# ethernet-cp2200.net
KiCad netlist of a schematic drawn in EAGLE
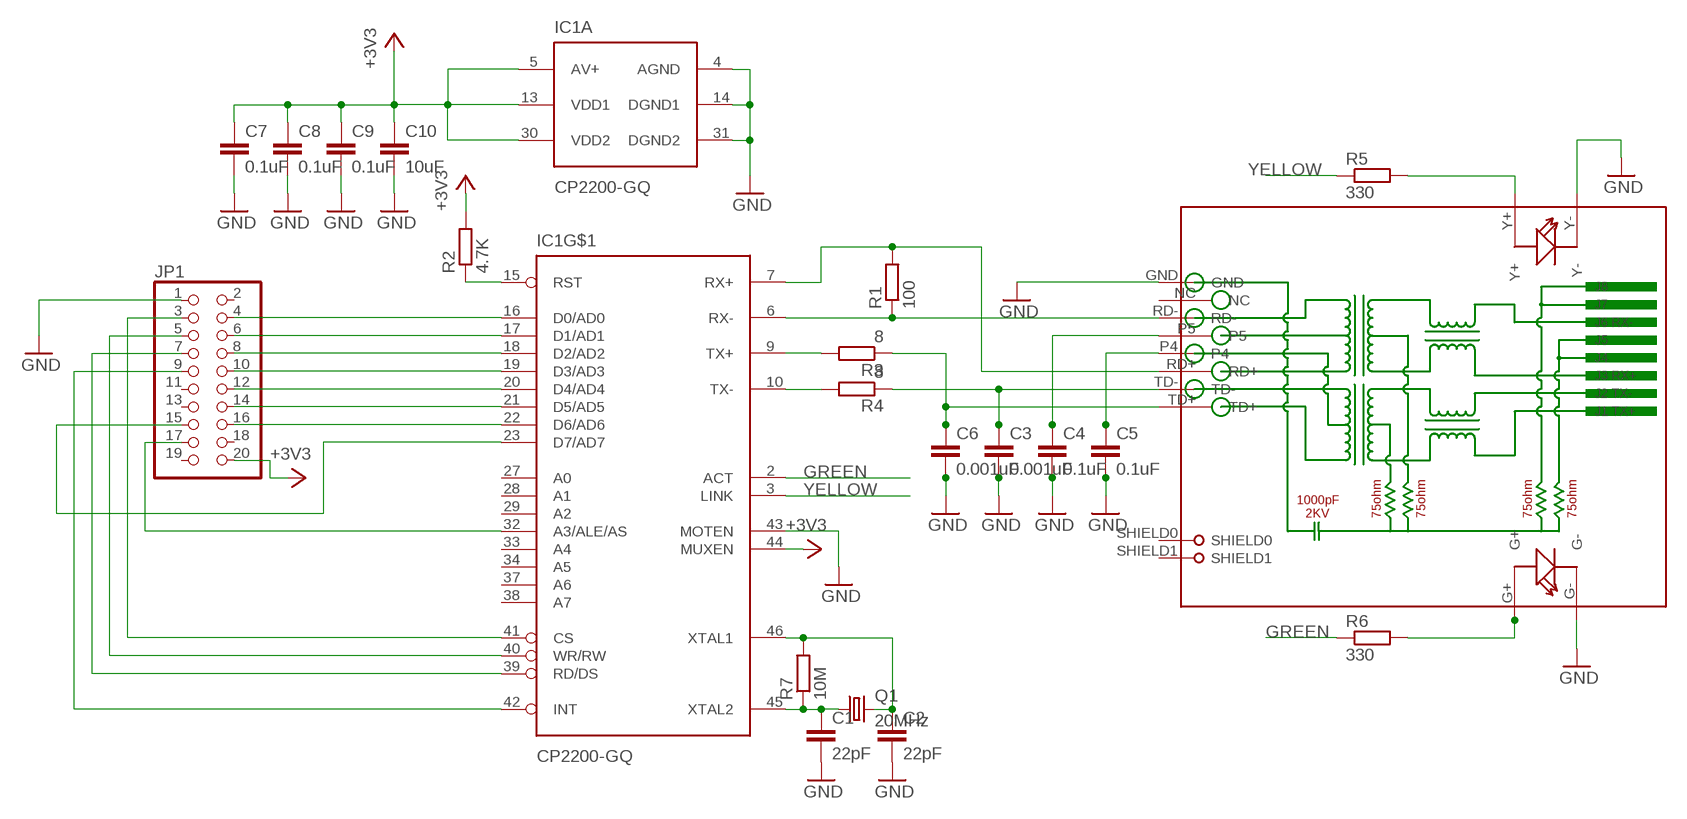
[diagram p0: schematic, sheet 1]

(export (version "E")
  (design (tool "Eeschema 10.0.6"))
  (components
    (comp (ref "C1")
      (value "22pF")
      (footprint "eagle-import:C0805")
      (libsource (lib "eagle-import") (part "C-EUC0805"))
    )
    (comp (ref "C2")
      (value "22pF")
      (footprint "eagle-import:C0805")
      (libsource (lib "eagle-import") (part "C-EUC0805"))
    )
    (comp (ref "C3")
      (value "0.001uF")
      (footprint "eagle-import:C0805")
      (libsource (lib "eagle-import") (part "C-EUC0805"))
    )
    (comp (ref "C4")
      (value "0.1uF")
      (footprint "eagle-import:C0805")
      (libsource (lib "eagle-import") (part "C-EUC0805"))
    )
    (comp (ref "C5")
      (value "0.1uF")
      (footprint "eagle-import:C0805")
      (libsource (lib "eagle-import") (part "C-EUC0805"))
    )
    (comp (ref "C6")
      (value "0.001uF")
      (footprint "eagle-import:C0805")
      (libsource (lib "eagle-import") (part "C-EUC0805"))
    )
    (comp (ref "C7")
      (value "0.1uF")
      (footprint "eagle-import:C0805")
      (libsource (lib "eagle-import") (part "C-EUC0805"))
    )
    (comp (ref "C8")
      (value "0.1uF")
      (footprint "eagle-import:C0805")
      (libsource (lib "eagle-import") (part "C-EUC0805"))
    )
    (comp (ref "C9")
      (value "0.1uF")
      (footprint "eagle-import:C0805")
      (libsource (lib "eagle-import") (part "C-EUC0805"))
    )
    (comp (ref "C10")
      (value "10uF")
      (footprint "eagle-import:C0805")
      (libsource (lib "eagle-import") (part "C-EUC0805"))
    )
    (comp (ref "IC1")
      (value "CP2200-GQ")
      (footprint "eagle-import:TQFP-48")
      (libsource (lib "eagle-import") (part "CP2200-GQ"))
    )
    (comp (ref "JP1")
      (value "PINHD-2X10")
      (footprint "eagle-import:2X10")
      (libsource (lib "eagle-import") (part "PINHD-2X10"))
    )
    (comp (ref "Q1")
      (value "20MHz")
      (footprint "eagle-import:HC49_S")
      (libsource (lib "eagle-import") (part "CRYSTALHC49S"))
    )
    (comp (ref "R1")
      (value "100")
      (footprint "eagle-import:M0805")
      (libsource (lib "eagle-import") (part "R-EU_M0805"))
    )
    (comp (ref "R2")
      (value "4.7K")
      (footprint "eagle-import:M0805")
      (libsource (lib "eagle-import") (part "R-EU_M0805"))
    )
    (comp (ref "R3")
      (value "8")
      (footprint "eagle-import:M0805")
      (libsource (lib "eagle-import") (part "R-EU_M0805"))
    )
    (comp (ref "R4")
      (value "8")
      (footprint "eagle-import:M0805")
      (libsource (lib "eagle-import") (part "R-EU_M0805"))
    )
    (comp (ref "R5")
      (value "330")
      (footprint "eagle-import:M0805")
      (libsource (lib "eagle-import") (part "R-EU_M0805"))
    )
    (comp (ref "R6")
      (value "330")
      (footprint "eagle-import:M0805")
      (libsource (lib "eagle-import") (part "R-EU_M0805"))
    )
    (comp (ref "R7")
      (value "10M")
      (footprint "eagle-import:M0805")
      (libsource (lib "eagle-import") (part "R-EU_M0805"))
    )
    (comp (ref "RJ1")
      (value "HR911105A")
      (footprint "eagle-import:HR911105A")
      (libsource (lib "eagle-import") (part "HR911105A"))
    )
  )
  (nets
    (net (code "1") (name "+3V3") (class "Default")
      (node (ref "C10") (pin "1") (pinfunction "1_1") (pintype "passive"))
      (node (ref "C7") (pin "1") (pinfunction "1_1") (pintype "passive"))
      (node (ref "C8") (pin "1") (pinfunction "1_1") (pintype "passive"))
      (node (ref "C9") (pin "1") (pinfunction "1_1") (pintype "passive"))
      (node (ref "IC1") (pin "13") (pinfunction "VDD1_13") (pintype "power_in"))
      (node (ref "IC1") (pin "30") (pinfunction "VDD2_30") (pintype "power_in"))
      (node (ref "IC1") (pin "44") (pinfunction "MUXEN_44") (pintype "input"))
      (node (ref "IC1") (pin "5") (pinfunction "AV+_5") (pintype "power_in"))
      (node (ref "JP1") (pin "20") (pinfunction "20_20") (pintype "passive"))
      (node (ref "R2") (pin "2") (pinfunction "2_2") (pintype "passive"))
    )
    (net (code "2") (name "/GREEN") (class "Default")
      (node (ref "IC1") (pin "2") (pinfunction "ACT_2") (pintype "output"))
      (node (ref "R6") (pin "1") (pinfunction "1_1") (pintype "passive"))
    )
    (net (code "3") (name "/YELLOW") (class "Default")
      (node (ref "IC1") (pin "3") (pinfunction "LINK_3") (pintype "output"))
      (node (ref "R5") (pin "1") (pinfunction "1_1") (pintype "passive"))
    )
    (net (code "4") (name "GND") (class "Default")
      (node (ref "C1") (pin "2") (pinfunction "2_2") (pintype "passive"))
      (node (ref "C10") (pin "2") (pinfunction "2_2") (pintype "passive"))
      (node (ref "C2") (pin "2") (pinfunction "2_2") (pintype "passive"))
      (node (ref "C3") (pin "2") (pinfunction "2_2") (pintype "passive"))
      (node (ref "C4") (pin "2") (pinfunction "2_2") (pintype "passive"))
      (node (ref "C5") (pin "2") (pinfunction "2_2") (pintype "passive"))
      (node (ref "C6") (pin "2") (pinfunction "2_2") (pintype "passive"))
      (node (ref "C7") (pin "2") (pinfunction "2_2") (pintype "passive"))
      (node (ref "C8") (pin "2") (pinfunction "2_2") (pintype "passive"))
      (node (ref "C9") (pin "2") (pinfunction "2_2") (pintype "passive"))
      (node (ref "IC1") (pin "14") (pinfunction "DGND1_14") (pintype "power_in"))
      (node (ref "IC1") (pin "31") (pinfunction "DGND2_31") (pintype "power_in"))
      (node (ref "IC1") (pin "4") (pinfunction "AGND_4") (pintype "power_in"))
      (node (ref "IC1") (pin "43") (pinfunction "MOTEN_43") (pintype "input"))
      (node (ref "JP1") (pin "1") (pinfunction "1_1") (pintype "passive"))
      (node (ref "RJ1") (pin "G-") (pinfunction "G-_G-") (pintype "bidirectional"))
      (node (ref "RJ1") (pin "GND") (pinfunction "GND_GND") (pintype "bidirectional"))
      (node (ref "RJ1") (pin "Y-") (pinfunction "Y-_Y-") (pintype "bidirectional"))
    )
    (net (code "5") (name "Net-(C3-Pad1)") (class "Default")
      (node (ref "C3") (pin "1") (pinfunction "1_1") (pintype "passive"))
      (node (ref "R4") (pin "1") (pinfunction "1_1") (pintype "passive"))
      (node (ref "RJ1") (pin "TD-") (pinfunction "TD-_TD-") (pintype "bidirectional"))
    )
    (net (code "6") (name "Net-(C4-Pad1)") (class "Default")
      (node (ref "C4") (pin "1") (pinfunction "1_1") (pintype "passive"))
      (node (ref "RJ1") (pin "P5") (pinfunction "P5_P5") (pintype "bidirectional"))
    )
    (net (code "7") (name "Net-(C5-Pad1)") (class "Default")
      (node (ref "C5") (pin "1") (pinfunction "1_1") (pintype "passive"))
      (node (ref "RJ1") (pin "P4") (pinfunction "P4_P4") (pintype "bidirectional"))
    )
    (net (code "8") (name "Net-(C6-Pad1)") (class "Default")
      (node (ref "C6") (pin "1") (pinfunction "1_1") (pintype "passive"))
      (node (ref "R3") (pin "1") (pinfunction "1_1") (pintype "passive"))
      (node (ref "RJ1") (pin "TD+") (pinfunction "TD+_TD+") (pintype "bidirectional"))
    )
    (net (code "9") (name "Net-(IC1B-A3{slash}ALE{slash}AS)") (class "Default")
      (node (ref "IC1") (pin "32") (pinfunction "A3/ALE/AS_32") (pintype "input"))
      (node (ref "JP1") (pin "17") (pinfunction "17_17") (pintype "passive"))
    )
    (net (code "10") (name "Net-(IC1B-CS)") (class "Default")
      (node (ref "IC1") (pin "41") (pinfunction "CS_41") (pintype "input"))
      (node (ref "JP1") (pin "3") (pinfunction "3_3") (pintype "passive"))
    )
    (net (code "11") (name "Net-(IC1B-D0{slash}AD0)") (class "Default")
      (node (ref "IC1") (pin "16") (pinfunction "D0/AD0_16") (pintype "bidirectional"))
      (node (ref "JP1") (pin "4") (pinfunction "4_4") (pintype "passive"))
    )
    (net (code "12") (name "Net-(IC1B-D1{slash}AD1)") (class "Default")
      (node (ref "IC1") (pin "17") (pinfunction "D1/AD1_17") (pintype "bidirectional"))
      (node (ref "JP1") (pin "6") (pinfunction "6_6") (pintype "passive"))
    )
    (net (code "13") (name "Net-(IC1B-D2{slash}AD2)") (class "Default")
      (node (ref "IC1") (pin "18") (pinfunction "D2/AD2_18") (pintype "bidirectional"))
      (node (ref "JP1") (pin "8") (pinfunction "8_8") (pintype "passive"))
    )
    (net (code "14") (name "Net-(IC1B-D3{slash}AD3)") (class "Default")
      (node (ref "IC1") (pin "19") (pinfunction "D3/AD3_19") (pintype "bidirectional"))
      (node (ref "JP1") (pin "10") (pinfunction "10_10") (pintype "passive"))
    )
    (net (code "15") (name "Net-(IC1B-D4{slash}AD4)") (class "Default")
      (node (ref "IC1") (pin "20") (pinfunction "D4/AD4_20") (pintype "bidirectional"))
      (node (ref "JP1") (pin "12") (pinfunction "12_12") (pintype "passive"))
    )
    (net (code "16") (name "Net-(IC1B-D5{slash}AD5)") (class "Default")
      (node (ref "IC1") (pin "21") (pinfunction "D5/AD5_21") (pintype "bidirectional"))
      (node (ref "JP1") (pin "14") (pinfunction "14_14") (pintype "passive"))
    )
    (net (code "17") (name "Net-(IC1B-D6{slash}AD6)") (class "Default")
      (node (ref "IC1") (pin "22") (pinfunction "D6/AD6_22") (pintype "bidirectional"))
      (node (ref "JP1") (pin "16") (pinfunction "16_16") (pintype "passive"))
    )
    (net (code "18") (name "Net-(IC1B-D7{slash}AD7)") (class "Default")
      (node (ref "IC1") (pin "23") (pinfunction "D7/AD7_23") (pintype "bidirectional"))
      (node (ref "JP1") (pin "15") (pinfunction "15_15") (pintype "passive"))
    )
    (net (code "19") (name "Net-(IC1B-INT)") (class "Default")
      (node (ref "IC1") (pin "42") (pinfunction "INT_42") (pintype "output"))
      (node (ref "JP1") (pin "9") (pinfunction "9_9") (pintype "passive"))
    )
    (net (code "20") (name "Net-(IC1B-RD{slash}DS)") (class "Default")
      (node (ref "IC1") (pin "39") (pinfunction "RD/DS_39") (pintype "input"))
      (node (ref "JP1") (pin "7") (pinfunction "7_7") (pintype "passive"))
    )
    (net (code "21") (name "Net-(IC1B-RST)") (class "Default")
      (node (ref "IC1") (pin "15") (pinfunction "RST_15") (pintype "input"))
      (node (ref "R2") (pin "1") (pinfunction "1_1") (pintype "passive"))
    )
    (net (code "22") (name "Net-(IC1B-RX+)") (class "Default")
      (node (ref "IC1") (pin "7") (pinfunction "RX+_7") (pintype "input"))
      (node (ref "R1") (pin "2") (pinfunction "2_2") (pintype "passive"))
      (node (ref "RJ1") (pin "RD+") (pinfunction "RD+_RD+") (pintype "bidirectional"))
    )
    (net (code "23") (name "Net-(IC1B-RX-)") (class "Default")
      (node (ref "IC1") (pin "6") (pinfunction "RX-_6") (pintype "input"))
      (node (ref "R1") (pin "1") (pinfunction "1_1") (pintype "passive"))
      (node (ref "RJ1") (pin "RD-") (pinfunction "RD-_RD-") (pintype "bidirectional"))
    )
    (net (code "24") (name "Net-(IC1B-TX+)") (class "Default")
      (node (ref "IC1") (pin "9") (pinfunction "TX+_9") (pintype "output"))
      (node (ref "R3") (pin "2") (pinfunction "2_2") (pintype "passive"))
    )
    (net (code "25") (name "Net-(IC1B-TX-)") (class "Default")
      (node (ref "IC1") (pin "10") (pinfunction "TX-_10") (pintype "output"))
      (node (ref "R4") (pin "2") (pinfunction "2_2") (pintype "passive"))
    )
    (net (code "26") (name "Net-(IC1B-WR{slash}RW)") (class "Default")
      (node (ref "IC1") (pin "40") (pinfunction "WR/RW_40") (pintype "input"))
      (node (ref "JP1") (pin "5") (pinfunction "5_5") (pintype "passive"))
    )
    (net (code "27") (name "Net-(IC1B-XTAL1)") (class "Default")
      (node (ref "C2") (pin "1") (pinfunction "1_1") (pintype "passive"))
      (node (ref "IC1") (pin "46") (pinfunction "XTAL1_46") (pintype "input"))
      (node (ref "Q1") (pin "2") (pinfunction "2_2") (pintype "passive"))
      (node (ref "R7") (pin "2") (pinfunction "2_2") (pintype "passive"))
    )
    (net (code "28") (name "Net-(IC1B-XTAL2)") (class "Default")
      (node (ref "C1") (pin "1") (pinfunction "1_1") (pintype "passive"))
      (node (ref "IC1") (pin "45") (pinfunction "XTAL2_45") (pintype "output"))
      (node (ref "Q1") (pin "1") (pinfunction "1_1") (pintype "passive"))
      (node (ref "R7") (pin "1") (pinfunction "1_1") (pintype "passive"))
    )
    (net (code "29") (name "Net-(R5-Pad2)") (class "Default")
      (node (ref "R5") (pin "2") (pinfunction "2_2") (pintype "passive"))
      (node (ref "RJ1") (pin "Y+") (pinfunction "Y+_Y+") (pintype "bidirectional"))
    )
    (net (code "30") (name "Net-(R6-Pad2)") (class "Default")
      (node (ref "R6") (pin "2") (pinfunction "2_2") (pintype "passive"))
      (node (ref "RJ1") (pin "G+") (pinfunction "G+_G+") (pintype "bidirectional"))
    )
    (net (code "31") (name "unconnected-(IC1B-A0-Pad27)") (class "Default")
      (node (ref "IC1") (pin "27") (pinfunction "A0_27") (pintype "input"))
    )
    (net (code "32") (name "unconnected-(IC1B-A1-Pad28)") (class "Default")
      (node (ref "IC1") (pin "28") (pinfunction "A1_28") (pintype "input"))
    )
    (net (code "33") (name "unconnected-(IC1B-A2-Pad29)") (class "Default")
      (node (ref "IC1") (pin "29") (pinfunction "A2_29") (pintype "input"))
    )
    (net (code "34") (name "unconnected-(IC1B-A4-Pad33)") (class "Default")
      (node (ref "IC1") (pin "33") (pinfunction "A4_33") (pintype "input"))
    )
    (net (code "35") (name "unconnected-(IC1B-A5-Pad34)") (class "Default")
      (node (ref "IC1") (pin "34") (pinfunction "A5_34") (pintype "input"))
    )
    (net (code "36") (name "unconnected-(IC1B-A6-Pad37)") (class "Default")
      (node (ref "IC1") (pin "37") (pinfunction "A6_37") (pintype "input"))
    )
    (net (code "37") (name "unconnected-(IC1B-A7-Pad38)") (class "Default")
      (node (ref "IC1") (pin "38") (pinfunction "A7_38") (pintype "input"))
    )
    (net (code "38") (name "unconnected-(JP1-Pad2)") (class "Default")
      (node (ref "JP1") (pin "2") (pinfunction "2_2") (pintype "passive"))
    )
    (net (code "39") (name "unconnected-(JP1-Pad11)") (class "Default")
      (node (ref "JP1") (pin "11") (pinfunction "11_11") (pintype "passive"))
    )
    (net (code "40") (name "unconnected-(JP1-Pad13)") (class "Default")
      (node (ref "JP1") (pin "13") (pinfunction "13_13") (pintype "passive"))
    )
    (net (code "41") (name "unconnected-(JP1-Pad18)") (class "Default")
      (node (ref "JP1") (pin "18") (pinfunction "18_18") (pintype "passive"))
    )
    (net (code "42") (name "unconnected-(JP1-Pad19)") (class "Default")
      (node (ref "JP1") (pin "19") (pinfunction "19_19") (pintype "passive"))
    )
    (net (code "43") (name "unconnected-(RJ1-PadNC)") (class "Default")
      (node (ref "RJ1") (pin "NC") (pinfunction "NC_NC") (pintype "bidirectional"))
    )
    (net (code "44") (name "unconnected-(RJ1-PadSHIELD0)") (class "Default")
      (node (ref "RJ1") (pin "SHIELD0") (pinfunction "SHIELD0_SHIELD0") (pintype "bidirectional"))
    )
    (net (code "45") (name "unconnected-(RJ1-PadSHIELD1)") (class "Default")
      (node (ref "RJ1") (pin "SHIELD1") (pinfunction "SHIELD1_SHIELD1") (pintype "bidirectional"))
    )
  )
)
